# BoatSensor.net
KiCad netlist of a schematic drawn in Altium Designer
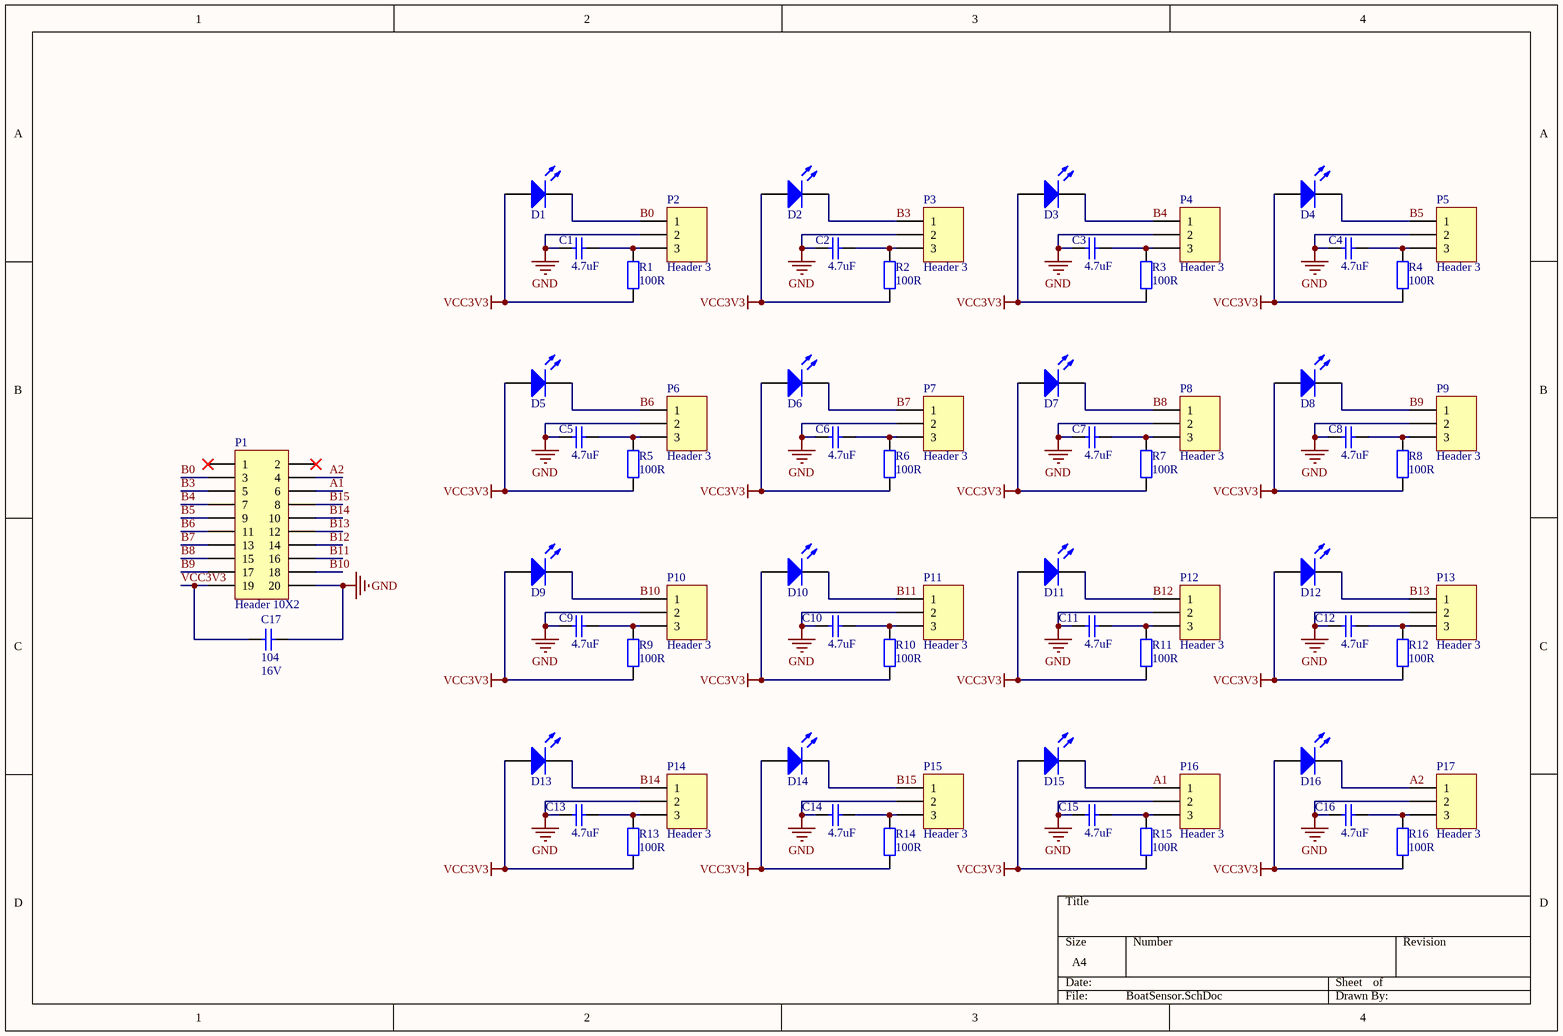
[diagram p0: BoatSensor.SchDoc]

(export (version "E")
  (design (tool "Eeschema 10.0.6"))
  (components
    (comp (ref "C1")
      (value "4.7uF")
      (footprint "0805")
      (fields (field (name "Comment") "Cap_2"))
      (libsource (lib "钦的集成库1") (part "Cap_2"))
    )
    (comp (ref "C2")
      (value "4.7uF")
      (footprint "0805")
      (fields (field (name "Comment") "Cap_2"))
      (libsource (lib "钦的集成库1") (part "Cap_2"))
    )
    (comp (ref "C3")
      (value "4.7uF")
      (footprint "0805")
      (fields (field (name "Comment") "Cap_2"))
      (libsource (lib "钦的集成库1") (part "Cap_2"))
    )
    (comp (ref "C4")
      (value "4.7uF")
      (footprint "0805")
      (fields (field (name "Comment") "Cap_2"))
      (libsource (lib "钦的集成库1") (part "Cap_2"))
    )
    (comp (ref "C5")
      (value "4.7uF")
      (footprint "0805")
      (fields (field (name "Comment") "Cap_2"))
      (libsource (lib "钦的集成库1") (part "Cap_2"))
    )
    (comp (ref "C6")
      (value "4.7uF")
      (footprint "0805")
      (fields (field (name "Comment") "Cap_2"))
      (libsource (lib "钦的集成库1") (part "Cap_2"))
    )
    (comp (ref "C7")
      (value "4.7uF")
      (footprint "0805")
      (fields (field (name "Comment") "Cap_2"))
      (libsource (lib "钦的集成库1") (part "Cap_2"))
    )
    (comp (ref "C8")
      (value "4.7uF")
      (footprint "0805")
      (fields (field (name "Comment") "Cap_2"))
      (libsource (lib "钦的集成库1") (part "Cap_2"))
    )
    (comp (ref "C9")
      (value "4.7uF")
      (footprint "0805")
      (fields (field (name "Comment") "Cap_2"))
      (libsource (lib "钦的集成库1") (part "Cap_2"))
    )
    (comp (ref "C10")
      (value "4.7uF")
      (footprint "0805")
      (fields (field (name "Comment") "Cap_2"))
      (libsource (lib "钦的集成库1") (part "Cap_2"))
    )
    (comp (ref "C11")
      (value "4.7uF")
      (footprint "0805")
      (fields (field (name "Comment") "Cap_2"))
      (libsource (lib "钦的集成库1") (part "Cap_2"))
    )
    (comp (ref "C12")
      (value "4.7uF")
      (footprint "0805")
      (fields (field (name "Comment") "Cap_2"))
      (libsource (lib "钦的集成库1") (part "Cap_2"))
    )
    (comp (ref "C13")
      (value "4.7uF")
      (footprint "0805")
      (fields (field (name "Comment") "Cap_2"))
      (libsource (lib "钦的集成库1") (part "Cap_2"))
    )
    (comp (ref "C14")
      (value "4.7uF")
      (footprint "0805")
      (fields (field (name "Comment") "Cap_2"))
      (libsource (lib "钦的集成库1") (part "Cap_2"))
    )
    (comp (ref "C15")
      (value "4.7uF")
      (footprint "0805")
      (fields (field (name "Comment") "Cap_2"))
      (libsource (lib "钦的集成库1") (part "Cap_2"))
    )
    (comp (ref "C16")
      (value "4.7uF")
      (footprint "0805")
      (fields (field (name "Comment") "Cap_2"))
      (libsource (lib "钦的集成库1") (part "Cap_2"))
    )
    (comp (ref "C17")
      (value "104")
      (footprint "0805")
      (fields
        (field (name "PRESSURE VOLTAGE") "16V")
        (field (name "Comment") "Cap")
        (field (name "原理图绘制者") "刘永钦")
        (field (name "原理图提供者") "刘永钦")
        (field (name "原理图审核人1") "徐鹏飞")
        (field (name "封装0805绘制者") "刘永钦")
        (field (name "封装0805提供者") "刘永钦")
        (field (name "封装0805审核人1") "徐鹏飞")
        (field (name "原理图审核人2") "朱觉文")
        (field (name "封装0805审核人2") "朱觉文")
        (field (name "封装0603绘制者") "刘永钦")
        (field (name "封装0603提供者") "刘永钦")
        (field (name "封装0603审核人1") "朱觉文")
        (field (name "封装0603审核人2") "徐鹏飞")
      )
      (libsource (lib "自动化研究所集成库20170403") (part "Cap"))
    )
    (comp (ref "D1")
      (value "LED")
      (footprint "LED_0805")
      (fields
        (field (name "原理图绘制者") "刘永钦")
        (field (name "原理图提供者") "刘永钦")
        (field (name "原理图审核人1") "徐鹏飞")
        (field (name "封装1210LED绘制者") "刘永钦")
        (field (name "封装1210LED提供者") "刘永钦")
        (field (name "封装1210LED审核人1") "徐鹏飞")
        (field (name "封装LED_3MM绘制者") "刘永钦")
        (field (name "封装LED_3MM提供者") "刘永钦")
        (field (name "封装LED_0805绘制者") "刘永钦")
        (field (name "封装LED_0805提供者") "刘永钦")
        (field (name "封装LED_0805审核人1") "徐鹏飞")
        (field (name "原理图审核人2") "朱觉文")
        (field (name "封装1210LED审核人2") "朱觉文")
        (field (name "封装LED_0805审核人2") "朱觉文")
        (field (name "封装LED_3MM审核者2") "朱觉文")
        (field (name "封装LED0603绘制者") "刘永钦")
        (field (name "封装LED0603审核人2") "朱觉文")
        (field (name "封装LED0603提供者") "刘永钦")
        (field (name "封装LED0603审核人1") "徐鹏飞")
      )
      (libsource (lib "自动化研究所集成库20170403") (part "LED"))
    )
    (comp (ref "D2")
      (value "LED")
      (footprint "LED_0805")
      (fields
        (field (name "原理图绘制者") "刘永钦")
        (field (name "原理图提供者") "刘永钦")
        (field (name "原理图审核人1") "徐鹏飞")
        (field (name "封装1210LED绘制者") "刘永钦")
        (field (name "封装1210LED提供者") "刘永钦")
        (field (name "封装1210LED审核人1") "徐鹏飞")
        (field (name "封装LED_3MM绘制者") "刘永钦")
        (field (name "封装LED_3MM提供者") "刘永钦")
        (field (name "封装LED_0805绘制者") "刘永钦")
        (field (name "封装LED_0805提供者") "刘永钦")
        (field (name "封装LED_0805审核人1") "徐鹏飞")
        (field (name "原理图审核人2") "朱觉文")
        (field (name "封装1210LED审核人2") "朱觉文")
        (field (name "封装LED_0805审核人2") "朱觉文")
        (field (name "封装LED_3MM审核者2") "朱觉文")
        (field (name "封装LED0603绘制者") "刘永钦")
        (field (name "封装LED0603审核人2") "朱觉文")
        (field (name "封装LED0603提供者") "刘永钦")
        (field (name "封装LED0603审核人1") "徐鹏飞")
      )
      (libsource (lib "自动化研究所集成库20170403") (part "LED"))
    )
    (comp (ref "D3")
      (value "LED")
      (footprint "LED_0805")
      (fields
        (field (name "原理图绘制者") "刘永钦")
        (field (name "原理图提供者") "刘永钦")
        (field (name "原理图审核人1") "徐鹏飞")
        (field (name "封装1210LED绘制者") "刘永钦")
        (field (name "封装1210LED提供者") "刘永钦")
        (field (name "封装1210LED审核人1") "徐鹏飞")
        (field (name "封装LED_3MM绘制者") "刘永钦")
        (field (name "封装LED_3MM提供者") "刘永钦")
        (field (name "封装LED_0805绘制者") "刘永钦")
        (field (name "封装LED_0805提供者") "刘永钦")
        (field (name "封装LED_0805审核人1") "徐鹏飞")
        (field (name "原理图审核人2") "朱觉文")
        (field (name "封装1210LED审核人2") "朱觉文")
        (field (name "封装LED_0805审核人2") "朱觉文")
        (field (name "封装LED_3MM审核者2") "朱觉文")
        (field (name "封装LED0603绘制者") "刘永钦")
        (field (name "封装LED0603审核人2") "朱觉文")
        (field (name "封装LED0603提供者") "刘永钦")
        (field (name "封装LED0603审核人1") "徐鹏飞")
      )
      (libsource (lib "自动化研究所集成库20170403") (part "LED"))
    )
    (comp (ref "D4")
      (value "LED")
      (footprint "LED_0805")
      (fields
        (field (name "原理图绘制者") "刘永钦")
        (field (name "原理图提供者") "刘永钦")
        (field (name "原理图审核人1") "徐鹏飞")
        (field (name "封装1210LED绘制者") "刘永钦")
        (field (name "封装1210LED提供者") "刘永钦")
        (field (name "封装1210LED审核人1") "徐鹏飞")
        (field (name "封装LED_3MM绘制者") "刘永钦")
        (field (name "封装LED_3MM提供者") "刘永钦")
        (field (name "封装LED_0805绘制者") "刘永钦")
        (field (name "封装LED_0805提供者") "刘永钦")
        (field (name "封装LED_0805审核人1") "徐鹏飞")
        (field (name "原理图审核人2") "朱觉文")
        (field (name "封装1210LED审核人2") "朱觉文")
        (field (name "封装LED_0805审核人2") "朱觉文")
        (field (name "封装LED_3MM审核者2") "朱觉文")
        (field (name "封装LED0603绘制者") "刘永钦")
        (field (name "封装LED0603审核人2") "朱觉文")
        (field (name "封装LED0603提供者") "刘永钦")
        (field (name "封装LED0603审核人1") "徐鹏飞")
      )
      (libsource (lib "自动化研究所集成库20170403") (part "LED"))
    )
    (comp (ref "D5")
      (value "LED")
      (footprint "LED_0805")
      (fields
        (field (name "原理图绘制者") "刘永钦")
        (field (name "原理图提供者") "刘永钦")
        (field (name "原理图审核人1") "徐鹏飞")
        (field (name "封装1210LED绘制者") "刘永钦")
        (field (name "封装1210LED提供者") "刘永钦")
        (field (name "封装1210LED审核人1") "徐鹏飞")
        (field (name "封装LED_3MM绘制者") "刘永钦")
        (field (name "封装LED_3MM提供者") "刘永钦")
        (field (name "封装LED_0805绘制者") "刘永钦")
        (field (name "封装LED_0805提供者") "刘永钦")
        (field (name "封装LED_0805审核人1") "徐鹏飞")
        (field (name "原理图审核人2") "朱觉文")
        (field (name "封装1210LED审核人2") "朱觉文")
        (field (name "封装LED_0805审核人2") "朱觉文")
        (field (name "封装LED_3MM审核者2") "朱觉文")
        (field (name "封装LED0603绘制者") "刘永钦")
        (field (name "封装LED0603审核人2") "朱觉文")
        (field (name "封装LED0603提供者") "刘永钦")
        (field (name "封装LED0603审核人1") "徐鹏飞")
      )
      (libsource (lib "自动化研究所集成库20170403") (part "LED"))
    )
    (comp (ref "D6")
      (value "LED")
      (footprint "LED_0805")
      (fields
        (field (name "原理图绘制者") "刘永钦")
        (field (name "原理图提供者") "刘永钦")
        (field (name "原理图审核人1") "徐鹏飞")
        (field (name "封装1210LED绘制者") "刘永钦")
        (field (name "封装1210LED提供者") "刘永钦")
        (field (name "封装1210LED审核人1") "徐鹏飞")
        (field (name "封装LED_3MM绘制者") "刘永钦")
        (field (name "封装LED_3MM提供者") "刘永钦")
        (field (name "封装LED_0805绘制者") "刘永钦")
        (field (name "封装LED_0805提供者") "刘永钦")
        (field (name "封装LED_0805审核人1") "徐鹏飞")
        (field (name "原理图审核人2") "朱觉文")
        (field (name "封装1210LED审核人2") "朱觉文")
        (field (name "封装LED_0805审核人2") "朱觉文")
        (field (name "封装LED_3MM审核者2") "朱觉文")
        (field (name "封装LED0603绘制者") "刘永钦")
        (field (name "封装LED0603审核人2") "朱觉文")
        (field (name "封装LED0603提供者") "刘永钦")
        (field (name "封装LED0603审核人1") "徐鹏飞")
      )
      (libsource (lib "自动化研究所集成库20170403") (part "LED"))
    )
    (comp (ref "D7")
      (value "LED")
      (footprint "LED_0805")
      (fields
        (field (name "原理图绘制者") "刘永钦")
        (field (name "原理图提供者") "刘永钦")
        (field (name "原理图审核人1") "徐鹏飞")
        (field (name "封装1210LED绘制者") "刘永钦")
        (field (name "封装1210LED提供者") "刘永钦")
        (field (name "封装1210LED审核人1") "徐鹏飞")
        (field (name "封装LED_3MM绘制者") "刘永钦")
        (field (name "封装LED_3MM提供者") "刘永钦")
        (field (name "封装LED_0805绘制者") "刘永钦")
        (field (name "封装LED_0805提供者") "刘永钦")
        (field (name "封装LED_0805审核人1") "徐鹏飞")
        (field (name "原理图审核人2") "朱觉文")
        (field (name "封装1210LED审核人2") "朱觉文")
        (field (name "封装LED_0805审核人2") "朱觉文")
        (field (name "封装LED_3MM审核者2") "朱觉文")
        (field (name "封装LED0603绘制者") "刘永钦")
        (field (name "封装LED0603审核人2") "朱觉文")
        (field (name "封装LED0603提供者") "刘永钦")
        (field (name "封装LED0603审核人1") "徐鹏飞")
      )
      (libsource (lib "自动化研究所集成库20170403") (part "LED"))
    )
    (comp (ref "D8")
      (value "LED")
      (footprint "LED_0805")
      (fields
        (field (name "原理图绘制者") "刘永钦")
        (field (name "原理图提供者") "刘永钦")
        (field (name "原理图审核人1") "徐鹏飞")
        (field (name "封装1210LED绘制者") "刘永钦")
        (field (name "封装1210LED提供者") "刘永钦")
        (field (name "封装1210LED审核人1") "徐鹏飞")
        (field (name "封装LED_3MM绘制者") "刘永钦")
        (field (name "封装LED_3MM提供者") "刘永钦")
        (field (name "封装LED_0805绘制者") "刘永钦")
        (field (name "封装LED_0805提供者") "刘永钦")
        (field (name "封装LED_0805审核人1") "徐鹏飞")
        (field (name "原理图审核人2") "朱觉文")
        (field (name "封装1210LED审核人2") "朱觉文")
        (field (name "封装LED_0805审核人2") "朱觉文")
        (field (name "封装LED_3MM审核者2") "朱觉文")
        (field (name "封装LED0603绘制者") "刘永钦")
        (field (name "封装LED0603审核人2") "朱觉文")
        (field (name "封装LED0603提供者") "刘永钦")
        (field (name "封装LED0603审核人1") "徐鹏飞")
      )
      (libsource (lib "自动化研究所集成库20170403") (part "LED"))
    )
    (comp (ref "D9")
      (value "LED")
      (footprint "LED_0805")
      (fields
        (field (name "原理图绘制者") "刘永钦")
        (field (name "原理图提供者") "刘永钦")
        (field (name "原理图审核人1") "徐鹏飞")
        (field (name "封装1210LED绘制者") "刘永钦")
        (field (name "封装1210LED提供者") "刘永钦")
        (field (name "封装1210LED审核人1") "徐鹏飞")
        (field (name "封装LED_3MM绘制者") "刘永钦")
        (field (name "封装LED_3MM提供者") "刘永钦")
        (field (name "封装LED_0805绘制者") "刘永钦")
        (field (name "封装LED_0805提供者") "刘永钦")
        (field (name "封装LED_0805审核人1") "徐鹏飞")
        (field (name "原理图审核人2") "朱觉文")
        (field (name "封装1210LED审核人2") "朱觉文")
        (field (name "封装LED_0805审核人2") "朱觉文")
        (field (name "封装LED_3MM审核者2") "朱觉文")
        (field (name "封装LED0603绘制者") "刘永钦")
        (field (name "封装LED0603审核人2") "朱觉文")
        (field (name "封装LED0603提供者") "刘永钦")
        (field (name "封装LED0603审核人1") "徐鹏飞")
      )
      (libsource (lib "自动化研究所集成库20170403") (part "LED"))
    )
    (comp (ref "D10")
      (value "LED")
      (footprint "LED_0805")
      (fields
        (field (name "原理图绘制者") "刘永钦")
        (field (name "原理图提供者") "刘永钦")
        (field (name "原理图审核人1") "徐鹏飞")
        (field (name "封装1210LED绘制者") "刘永钦")
        (field (name "封装1210LED提供者") "刘永钦")
        (field (name "封装1210LED审核人1") "徐鹏飞")
        (field (name "封装LED_3MM绘制者") "刘永钦")
        (field (name "封装LED_3MM提供者") "刘永钦")
        (field (name "封装LED_0805绘制者") "刘永钦")
        (field (name "封装LED_0805提供者") "刘永钦")
        (field (name "封装LED_0805审核人1") "徐鹏飞")
        (field (name "原理图审核人2") "朱觉文")
        (field (name "封装1210LED审核人2") "朱觉文")
        (field (name "封装LED_0805审核人2") "朱觉文")
        (field (name "封装LED_3MM审核者2") "朱觉文")
        (field (name "封装LED0603绘制者") "刘永钦")
        (field (name "封装LED0603审核人2") "朱觉文")
        (field (name "封装LED0603提供者") "刘永钦")
        (field (name "封装LED0603审核人1") "徐鹏飞")
      )
      (libsource (lib "自动化研究所集成库20170403") (part "LED"))
    )
    (comp (ref "D11")
      (value "LED")
      (footprint "LED_0805")
      (fields
        (field (name "原理图绘制者") "刘永钦")
        (field (name "原理图提供者") "刘永钦")
        (field (name "原理图审核人1") "徐鹏飞")
        (field (name "封装1210LED绘制者") "刘永钦")
        (field (name "封装1210LED提供者") "刘永钦")
        (field (name "封装1210LED审核人1") "徐鹏飞")
        (field (name "封装LED_3MM绘制者") "刘永钦")
        (field (name "封装LED_3MM提供者") "刘永钦")
        (field (name "封装LED_0805绘制者") "刘永钦")
        (field (name "封装LED_0805提供者") "刘永钦")
        (field (name "封装LED_0805审核人1") "徐鹏飞")
        (field (name "原理图审核人2") "朱觉文")
        (field (name "封装1210LED审核人2") "朱觉文")
        (field (name "封装LED_0805审核人2") "朱觉文")
        (field (name "封装LED_3MM审核者2") "朱觉文")
        (field (name "封装LED0603绘制者") "刘永钦")
        (field (name "封装LED0603审核人2") "朱觉文")
        (field (name "封装LED0603提供者") "刘永钦")
        (field (name "封装LED0603审核人1") "徐鹏飞")
      )
      (libsource (lib "自动化研究所集成库20170403") (part "LED"))
    )
    (comp (ref "D12")
      (value "LED")
      (footprint "LED_0805")
      (fields
        (field (name "原理图绘制者") "刘永钦")
        (field (name "原理图提供者") "刘永钦")
        (field (name "原理图审核人1") "徐鹏飞")
        (field (name "封装1210LED绘制者") "刘永钦")
        (field (name "封装1210LED提供者") "刘永钦")
        (field (name "封装1210LED审核人1") "徐鹏飞")
        (field (name "封装LED_3MM绘制者") "刘永钦")
        (field (name "封装LED_3MM提供者") "刘永钦")
        (field (name "封装LED_0805绘制者") "刘永钦")
        (field (name "封装LED_0805提供者") "刘永钦")
        (field (name "封装LED_0805审核人1") "徐鹏飞")
        (field (name "原理图审核人2") "朱觉文")
        (field (name "封装1210LED审核人2") "朱觉文")
        (field (name "封装LED_0805审核人2") "朱觉文")
        (field (name "封装LED_3MM审核者2") "朱觉文")
        (field (name "封装LED0603绘制者") "刘永钦")
        (field (name "封装LED0603审核人2") "朱觉文")
        (field (name "封装LED0603提供者") "刘永钦")
        (field (name "封装LED0603审核人1") "徐鹏飞")
      )
      (libsource (lib "自动化研究所集成库20170403") (part "LED"))
    )
    (comp (ref "D13")
      (value "LED")
      (footprint "LED_0805")
      (fields
        (field (name "原理图绘制者") "刘永钦")
        (field (name "原理图提供者") "刘永钦")
        (field (name "原理图审核人1") "徐鹏飞")
        (field (name "封装1210LED绘制者") "刘永钦")
        (field (name "封装1210LED提供者") "刘永钦")
        (field (name "封装1210LED审核人1") "徐鹏飞")
        (field (name "封装LED_3MM绘制者") "刘永钦")
        (field (name "封装LED_3MM提供者") "刘永钦")
        (field (name "封装LED_0805绘制者") "刘永钦")
        (field (name "封装LED_0805提供者") "刘永钦")
        (field (name "封装LED_0805审核人1") "徐鹏飞")
        (field (name "原理图审核人2") "朱觉文")
        (field (name "封装1210LED审核人2") "朱觉文")
        (field (name "封装LED_0805审核人2") "朱觉文")
        (field (name "封装LED_3MM审核者2") "朱觉文")
        (field (name "封装LED0603绘制者") "刘永钦")
        (field (name "封装LED0603审核人2") "朱觉文")
        (field (name "封装LED0603提供者") "刘永钦")
        (field (name "封装LED0603审核人1") "徐鹏飞")
      )
      (libsource (lib "自动化研究所集成库20170403") (part "LED"))
    )
    (comp (ref "D14")
      (value "LED")
      (footprint "LED_0805")
      (fields
        (field (name "原理图绘制者") "刘永钦")
        (field (name "原理图提供者") "刘永钦")
        (field (name "原理图审核人1") "徐鹏飞")
        (field (name "封装1210LED绘制者") "刘永钦")
        (field (name "封装1210LED提供者") "刘永钦")
        (field (name "封装1210LED审核人1") "徐鹏飞")
        (field (name "封装LED_3MM绘制者") "刘永钦")
        (field (name "封装LED_3MM提供者") "刘永钦")
        (field (name "封装LED_0805绘制者") "刘永钦")
        (field (name "封装LED_0805提供者") "刘永钦")
        (field (name "封装LED_0805审核人1") "徐鹏飞")
        (field (name "原理图审核人2") "朱觉文")
        (field (name "封装1210LED审核人2") "朱觉文")
        (field (name "封装LED_0805审核人2") "朱觉文")
        (field (name "封装LED_3MM审核者2") "朱觉文")
        (field (name "封装LED0603绘制者") "刘永钦")
        (field (name "封装LED0603审核人2") "朱觉文")
        (field (name "封装LED0603提供者") "刘永钦")
        (field (name "封装LED0603审核人1") "徐鹏飞")
      )
      (libsource (lib "自动化研究所集成库20170403") (part "LED"))
    )
    (comp (ref "D15")
      (value "LED")
      (footprint "LED_0805")
      (fields
        (field (name "原理图绘制者") "刘永钦")
        (field (name "原理图提供者") "刘永钦")
        (field (name "原理图审核人1") "徐鹏飞")
        (field (name "封装1210LED绘制者") "刘永钦")
        (field (name "封装1210LED提供者") "刘永钦")
        (field (name "封装1210LED审核人1") "徐鹏飞")
        (field (name "封装LED_3MM绘制者") "刘永钦")
        (field (name "封装LED_3MM提供者") "刘永钦")
        (field (name "封装LED_0805绘制者") "刘永钦")
        (field (name "封装LED_0805提供者") "刘永钦")
        (field (name "封装LED_0805审核人1") "徐鹏飞")
        (field (name "原理图审核人2") "朱觉文")
        (field (name "封装1210LED审核人2") "朱觉文")
        (field (name "封装LED_0805审核人2") "朱觉文")
        (field (name "封装LED_3MM审核者2") "朱觉文")
        (field (name "封装LED0603绘制者") "刘永钦")
        (field (name "封装LED0603审核人2") "朱觉文")
        (field (name "封装LED0603提供者") "刘永钦")
        (field (name "封装LED0603审核人1") "徐鹏飞")
      )
      (libsource (lib "自动化研究所集成库20170403") (part "LED"))
    )
    (comp (ref "D16")
      (value "LED")
      (footprint "LED_0805")
      (fields
        (field (name "原理图绘制者") "刘永钦")
        (field (name "原理图提供者") "刘永钦")
        (field (name "原理图审核人1") "徐鹏飞")
        (field (name "封装1210LED绘制者") "刘永钦")
        (field (name "封装1210LED提供者") "刘永钦")
        (field (name "封装1210LED审核人1") "徐鹏飞")
        (field (name "封装LED_3MM绘制者") "刘永钦")
        (field (name "封装LED_3MM提供者") "刘永钦")
        (field (name "封装LED_0805绘制者") "刘永钦")
        (field (name "封装LED_0805提供者") "刘永钦")
        (field (name "封装LED_0805审核人1") "徐鹏飞")
        (field (name "原理图审核人2") "朱觉文")
        (field (name "封装1210LED审核人2") "朱觉文")
        (field (name "封装LED_0805审核人2") "朱觉文")
        (field (name "封装LED_3MM审核者2") "朱觉文")
        (field (name "封装LED0603绘制者") "刘永钦")
        (field (name "封装LED0603审核人2") "朱觉文")
        (field (name "封装LED0603提供者") "刘永钦")
        (field (name "封装LED0603审核人1") "徐鹏飞")
      )
      (libsource (lib "自动化研究所集成库20170403") (part "LED"))
    )
    (comp (ref "P1")
      (value "Header 10X2")
      (footprint "HDR2X10")
      (description "Header, 10-Pin, Dual row")
      (fields (field (name "PUBLISHER") "Altium Limited"))
      (libsource (lib "Miscellaneous Connectors") (part "Header 10X2"))
    )
    (comp (ref "P2")
      (value "Header 3")
      (footprint "HDR1X3")
      (description "Header, 3-Pin")
      (fields (field (name "PUBLISHER") "Altium Limited"))
      (libsource (lib "Miscellaneous Connectors") (part "Header 3"))
    )
    (comp (ref "P3")
      (value "Header 3")
      (footprint "HDR1X3")
      (description "Header, 3-Pin")
      (fields (field (name "PUBLISHER") "Altium Limited"))
      (libsource (lib "Miscellaneous Connectors") (part "Header 3"))
    )
    (comp (ref "P4")
      (value "Header 3")
      (footprint "HDR1X3")
      (description "Header, 3-Pin")
      (fields (field (name "PUBLISHER") "Altium Limited"))
      (libsource (lib "Miscellaneous Connectors") (part "Header 3"))
    )
    (comp (ref "P5")
      (value "Header 3")
      (footprint "HDR1X3")
      (description "Header, 3-Pin")
      (fields (field (name "PUBLISHER") "Altium Limited"))
      (libsource (lib "Miscellaneous Connectors") (part "Header 3"))
    )
    (comp (ref "P6")
      (value "Header 3")
      (footprint "HDR1X3")
      (description "Header, 3-Pin")
      (fields (field (name "PUBLISHER") "Altium Limited"))
      (libsource (lib "Miscellaneous Connectors") (part "Header 3"))
    )
    (comp (ref "P7")
      (value "Header 3")
      (footprint "HDR1X3")
      (description "Header, 3-Pin")
      (fields (field (name "PUBLISHER") "Altium Limited"))
      (libsource (lib "Miscellaneous Connectors") (part "Header 3"))
    )
    (comp (ref "P8")
      (value "Header 3")
      (footprint "HDR1X3")
      (description "Header, 3-Pin")
      (fields (field (name "PUBLISHER") "Altium Limited"))
      (libsource (lib "Miscellaneous Connectors") (part "Header 3"))
    )
    (comp (ref "P9")
      (value "Header 3")
      (footprint "HDR1X3")
      (description "Header, 3-Pin")
      (fields (field (name "PUBLISHER") "Altium Limited"))
      (libsource (lib "Miscellaneous Connectors") (part "Header 3"))
    )
    (comp (ref "P10")
      (value "Header 3")
      (footprint "HDR1X3")
      (description "Header, 3-Pin")
      (fields (field (name "PUBLISHER") "Altium Limited"))
      (libsource (lib "Miscellaneous Connectors") (part "Header 3"))
    )
    (comp (ref "P11")
      (value "Header 3")
      (footprint "HDR1X3")
      (description "Header, 3-Pin")
      (fields (field (name "PUBLISHER") "Altium Limited"))
      (libsource (lib "Miscellaneous Connectors") (part "Header 3"))
    )
    (comp (ref "P12")
      (value "Header 3")
      (footprint "HDR1X3")
      (description "Header, 3-Pin")
      (fields (field (name "PUBLISHER") "Altium Limited"))
      (libsource (lib "Miscellaneous Connectors") (part "Header 3"))
    )
    (comp (ref "P13")
      (value "Header 3")
      (footprint "HDR1X3")
      (description "Header, 3-Pin")
      (fields (field (name "PUBLISHER") "Altium Limited"))
      (libsource (lib "Miscellaneous Connectors") (part "Header 3"))
    )
    (comp (ref "P14")
      (value "Header 3")
      (footprint "HDR1X3")
      (description "Header, 3-Pin")
      (fields (field (name "PUBLISHER") "Altium Limited"))
      (libsource (lib "Miscellaneous Connectors") (part "Header 3"))
    )
    (comp (ref "P15")
      (value "Header 3")
      (footprint "HDR1X3")
      (description "Header, 3-Pin")
      (fields (field (name "PUBLISHER") "Altium Limited"))
      (libsource (lib "Miscellaneous Connectors") (part "Header 3"))
    )
    (comp (ref "P16")
      (value "Header 3")
      (footprint "HDR1X3")
      (description "Header, 3-Pin")
      (fields (field (name "PUBLISHER") "Altium Limited"))
      (libsource (lib "Miscellaneous Connectors") (part "Header 3"))
    )
    (comp (ref "P17")
      (value "Header 3")
      (footprint "HDR1X3")
      (description "Header, 3-Pin")
      (fields (field (name "PUBLISHER") "Altium Limited"))
      (libsource (lib "Miscellaneous Connectors") (part "Header 3"))
    )
    (comp (ref "R1")
      (value "100R")
      (footprint "0805")
      (fields (field (name "Comment") "Res_"))
      (libsource (lib "钦的集成库1") (part "Res_"))
    )
    (comp (ref "R2")
      (value "100R")
      (footprint "0805")
      (fields (field (name "Comment") "Res_"))
      (libsource (lib "钦的集成库1") (part "Res_"))
    )
    (comp (ref "R3")
      (value "100R")
      (footprint "0805")
      (fields (field (name "Comment") "Res_"))
      (libsource (lib "钦的集成库1") (part "Res_"))
    )
    (comp (ref "R4")
      (value "100R")
      (footprint "0805")
      (fields (field (name "Comment") "Res_"))
      (libsource (lib "钦的集成库1") (part "Res_"))
    )
    (comp (ref "R5")
      (value "100R")
      (footprint "0805")
      (fields (field (name "Comment") "Res_"))
      (libsource (lib "钦的集成库1") (part "Res_"))
    )
    (comp (ref "R6")
      (value "100R")
      (footprint "0805")
      (fields (field (name "Comment") "Res_"))
      (libsource (lib "钦的集成库1") (part "Res_"))
    )
    (comp (ref "R7")
      (value "100R")
      (footprint "0805")
      (fields (field (name "Comment") "Res_"))
      (libsource (lib "钦的集成库1") (part "Res_"))
    )
    (comp (ref "R8")
      (value "100R")
      (footprint "0805")
      (fields (field (name "Comment") "Res_"))
      (libsource (lib "钦的集成库1") (part "Res_"))
    )
    (comp (ref "R9")
      (value "100R")
      (footprint "0805")
      (fields (field (name "Comment") "Res_"))
      (libsource (lib "钦的集成库1") (part "Res_"))
    )
    (comp (ref "R10")
      (value "100R")
      (footprint "0805")
      (fields (field (name "Comment") "Res_"))
      (libsource (lib "钦的集成库1") (part "Res_"))
    )
    (comp (ref "R11")
      (value "100R")
      (footprint "0805")
      (fields (field (name "Comment") "Res_"))
      (libsource (lib "钦的集成库1") (part "Res_"))
    )
    (comp (ref "R12")
      (value "100R")
      (footprint "0805")
      (fields (field (name "Comment") "Res_"))
      (libsource (lib "钦的集成库1") (part "Res_"))
    )
    (comp (ref "R13")
      (value "100R")
      (footprint "0805")
      (fields (field (name "Comment") "Res_"))
      (libsource (lib "钦的集成库1") (part "Res_"))
    )
    (comp (ref "R14")
      (value "100R")
      (footprint "0805")
      (fields (field (name "Comment") "Res_"))
      (libsource (lib "钦的集成库1") (part "Res_"))
    )
    (comp (ref "R15")
      (value "100R")
      (footprint "0805")
      (fields (field (name "Comment") "Res_"))
      (libsource (lib "钦的集成库1") (part "Res_"))
    )
    (comp (ref "R16")
      (value "100R")
      (footprint "0805")
      (fields (field (name "Comment") "Res_"))
      (libsource (lib "钦的集成库1") (part "Res_"))
    )
  )
  (nets
    (net (code "1") (name "/A1") (class "Default")
      (node (ref "D15") (pin "2") (pinfunction "K_2") (pintype "passive"))
      (node (ref "P1") (pin "6") (pinfunction "6_6") (pintype "passive"))
      (node (ref "P16") (pin "1") (pinfunction "1_1") (pintype "passive"))
    )
    (net (code "2") (name "/A2") (class "Default")
      (node (ref "D16") (pin "2") (pinfunction "K_2") (pintype "passive"))
      (node (ref "P1") (pin "4") (pinfunction "4_4") (pintype "passive"))
      (node (ref "P17") (pin "1") (pinfunction "1_1") (pintype "passive"))
    )
    (net (code "3") (name "/B0") (class "Default")
      (node (ref "D1") (pin "2") (pinfunction "K_2") (pintype "passive"))
      (node (ref "P1") (pin "3") (pinfunction "3_3") (pintype "passive"))
      (node (ref "P2") (pin "1") (pinfunction "1_1") (pintype "passive"))
    )
    (net (code "4") (name "/B3") (class "Default")
      (node (ref "D2") (pin "2") (pinfunction "K_2") (pintype "passive"))
      (node (ref "P1") (pin "5") (pinfunction "5_5") (pintype "passive"))
      (node (ref "P3") (pin "1") (pinfunction "1_1") (pintype "passive"))
    )
    (net (code "5") (name "/B4") (class "Default")
      (node (ref "D3") (pin "2") (pinfunction "K_2") (pintype "passive"))
      (node (ref "P1") (pin "7") (pinfunction "7_7") (pintype "passive"))
      (node (ref "P4") (pin "1") (pinfunction "1_1") (pintype "passive"))
    )
    (net (code "6") (name "/B5") (class "Default")
      (node (ref "D4") (pin "2") (pinfunction "K_2") (pintype "passive"))
      (node (ref "P1") (pin "9") (pinfunction "9_9") (pintype "passive"))
      (node (ref "P5") (pin "1") (pinfunction "1_1") (pintype "passive"))
    )
    (net (code "7") (name "/B6") (class "Default")
      (node (ref "D5") (pin "2") (pinfunction "K_2") (pintype "passive"))
      (node (ref "P1") (pin "11") (pinfunction "11_11") (pintype "passive"))
      (node (ref "P6") (pin "1") (pinfunction "1_1") (pintype "passive"))
    )
    (net (code "8") (name "/B7") (class "Default")
      (node (ref "D6") (pin "2") (pinfunction "K_2") (pintype "passive"))
      (node (ref "P1") (pin "13") (pinfunction "13_13") (pintype "passive"))
      (node (ref "P7") (pin "1") (pinfunction "1_1") (pintype "passive"))
    )
    (net (code "9") (name "/B8") (class "Default")
      (node (ref "D7") (pin "2") (pinfunction "K_2") (pintype "passive"))
      (node (ref "P1") (pin "15") (pinfunction "15_15") (pintype "passive"))
      (node (ref "P8") (pin "1") (pinfunction "1_1") (pintype "passive"))
    )
    (net (code "10") (name "/B9") (class "Default")
      (node (ref "D8") (pin "2") (pinfunction "K_2") (pintype "passive"))
      (node (ref "P1") (pin "17") (pinfunction "17_17") (pintype "passive"))
      (node (ref "P9") (pin "1") (pinfunction "1_1") (pintype "passive"))
    )
    (net (code "11") (name "/B10") (class "Default")
      (node (ref "D9") (pin "2") (pinfunction "K_2") (pintype "passive"))
      (node (ref "P1") (pin "18") (pinfunction "18_18") (pintype "passive"))
      (node (ref "P10") (pin "1") (pinfunction "1_1") (pintype "passive"))
    )
    (net (code "12") (name "/B11") (class "Default")
      (node (ref "D10") (pin "2") (pinfunction "K_2") (pintype "passive"))
      (node (ref "P1") (pin "16") (pinfunction "16_16") (pintype "passive"))
      (node (ref "P11") (pin "1") (pinfunction "1_1") (pintype "passive"))
    )
    (net (code "13") (name "/B12") (class "Default")
      (node (ref "D11") (pin "2") (pinfunction "K_2") (pintype "passive"))
      (node (ref "P1") (pin "14") (pinfunction "14_14") (pintype "passive"))
      (node (ref "P12") (pin "1") (pinfunction "1_1") (pintype "passive"))
    )
    (net (code "14") (name "/B13") (class "Default")
      (node (ref "D12") (pin "2") (pinfunction "K_2") (pintype "passive"))
      (node (ref "P1") (pin "12") (pinfunction "12_12") (pintype "passive"))
      (node (ref "P13") (pin "1") (pinfunction "1_1") (pintype "passive"))
    )
    (net (code "15") (name "/B14") (class "Default")
      (node (ref "D13") (pin "2") (pinfunction "K_2") (pintype "passive"))
      (node (ref "P1") (pin "10") (pinfunction "10_10") (pintype "passive"))
      (node (ref "P14") (pin "1") (pinfunction "1_1") (pintype "passive"))
    )
    (net (code "16") (name "/B15") (class "Default")
      (node (ref "D14") (pin "2") (pinfunction "K_2") (pintype "passive"))
      (node (ref "P1") (pin "8") (pinfunction "8_8") (pintype "passive"))
      (node (ref "P15") (pin "1") (pinfunction "1_1") (pintype "passive"))
    )
    (net (code "17") (name "GND") (class "Default")
      (node (ref "C1") (pin "2") (pinfunction "2_2") (pintype "passive"))
      (node (ref "C10") (pin "2") (pinfunction "2_2") (pintype "passive"))
      (node (ref "C11") (pin "2") (pinfunction "2_2") (pintype "passive"))
      (node (ref "C12") (pin "2") (pinfunction "2_2") (pintype "passive"))
      (node (ref "C13") (pin "2") (pinfunction "2_2") (pintype "passive"))
      (node (ref "C14") (pin "2") (pinfunction "2_2") (pintype "passive"))
      (node (ref "C15") (pin "2") (pinfunction "2_2") (pintype "passive"))
      (node (ref "C16") (pin "2") (pinfunction "2_2") (pintype "passive"))
      (node (ref "C17") (pin "2") (pinfunction "2_2") (pintype "passive"))
      (node (ref "C2") (pin "2") (pinfunction "2_2") (pintype "passive"))
      (node (ref "C3") (pin "2") (pinfunction "2_2") (pintype "passive"))
      (node (ref "C4") (pin "2") (pinfunction "2_2") (pintype "passive"))
      (node (ref "C5") (pin "2") (pinfunction "2_2") (pintype "passive"))
      (node (ref "C6") (pin "2") (pinfunction "2_2") (pintype "passive"))
      (node (ref "C7") (pin "2") (pinfunction "2_2") (pintype "passive"))
      (node (ref "C8") (pin "2") (pinfunction "2_2") (pintype "passive"))
      (node (ref "C9") (pin "2") (pinfunction "2_2") (pintype "passive"))
      (node (ref "P1") (pin "20") (pinfunction "20_20") (pintype "passive"))
      (node (ref "P10") (pin "2") (pinfunction "2_2") (pintype "passive"))
      (node (ref "P11") (pin "2") (pinfunction "2_2") (pintype "passive"))
      (node (ref "P12") (pin "2") (pinfunction "2_2") (pintype "passive"))
      (node (ref "P13") (pin "2") (pinfunction "2_2") (pintype "passive"))
      (node (ref "P14") (pin "2") (pinfunction "2_2") (pintype "passive"))
      (node (ref "P15") (pin "2") (pinfunction "2_2") (pintype "passive"))
      (node (ref "P16") (pin "2") (pinfunction "2_2") (pintype "passive"))
      (node (ref "P17") (pin "2") (pinfunction "2_2") (pintype "passive"))
      (node (ref "P2") (pin "2") (pinfunction "2_2") (pintype "passive"))
      (node (ref "P3") (pin "2") (pinfunction "2_2") (pintype "passive"))
      (node (ref "P4") (pin "2") (pinfunction "2_2") (pintype "passive"))
      (node (ref "P5") (pin "2") (pinfunction "2_2") (pintype "passive"))
      (node (ref "P6") (pin "2") (pinfunction "2_2") (pintype "passive"))
      (node (ref "P7") (pin "2") (pinfunction "2_2") (pintype "passive"))
      (node (ref "P8") (pin "2") (pinfunction "2_2") (pintype "passive"))
      (node (ref "P9") (pin "2") (pinfunction "2_2") (pintype "passive"))
    )
    (net (code "18") (name "Net-(C1-Pad1)") (class "Default")
      (node (ref "C1") (pin "1") (pinfunction "1_1") (pintype "passive"))
      (node (ref "P2") (pin "3") (pinfunction "3_3") (pintype "passive"))
      (node (ref "R1") (pin "1") (pinfunction "1_1") (pintype "passive"))
    )
    (net (code "19") (name "Net-(C2-Pad1)") (class "Default")
      (node (ref "C2") (pin "1") (pinfunction "1_1") (pintype "passive"))
      (node (ref "P3") (pin "3") (pinfunction "3_3") (pintype "passive"))
      (node (ref "R2") (pin "1") (pinfunction "1_1") (pintype "passive"))
    )
    (net (code "20") (name "Net-(C3-Pad1)") (class "Default")
      (node (ref "C3") (pin "1") (pinfunction "1_1") (pintype "passive"))
      (node (ref "P4") (pin "3") (pinfunction "3_3") (pintype "passive"))
      (node (ref "R3") (pin "1") (pinfunction "1_1") (pintype "passive"))
    )
    (net (code "21") (name "Net-(C4-Pad1)") (class "Default")
      (node (ref "C4") (pin "1") (pinfunction "1_1") (pintype "passive"))
      (node (ref "P5") (pin "3") (pinfunction "3_3") (pintype "passive"))
      (node (ref "R4") (pin "1") (pinfunction "1_1") (pintype "passive"))
    )
    (net (code "22") (name "Net-(C5-Pad1)") (class "Default")
      (node (ref "C5") (pin "1") (pinfunction "1_1") (pintype "passive"))
      (node (ref "P6") (pin "3") (pinfunction "3_3") (pintype "passive"))
      (node (ref "R5") (pin "1") (pinfunction "1_1") (pintype "passive"))
    )
    (net (code "23") (name "Net-(C6-Pad1)") (class "Default")
      (node (ref "C6") (pin "1") (pinfunction "1_1") (pintype "passive"))
      (node (ref "P7") (pin "3") (pinfunction "3_3") (pintype "passive"))
      (node (ref "R6") (pin "1") (pinfunction "1_1") (pintype "passive"))
    )
    (net (code "24") (name "Net-(C7-Pad1)") (class "Default")
      (node (ref "C7") (pin "1") (pinfunction "1_1") (pintype "passive"))
      (node (ref "P8") (pin "3") (pinfunction "3_3") (pintype "passive"))
      (node (ref "R7") (pin "1") (pinfunction "1_1") (pintype "passive"))
    )
    (net (code "25") (name "Net-(C8-Pad1)") (class "Default")
      (node (ref "C8") (pin "1") (pinfunction "1_1") (pintype "passive"))
      (node (ref "P9") (pin "3") (pinfunction "3_3") (pintype "passive"))
      (node (ref "R8") (pin "1") (pinfunction "1_1") (pintype "passive"))
    )
    (net (code "26") (name "Net-(C9-Pad1)") (class "Default")
      (node (ref "C9") (pin "1") (pinfunction "1_1") (pintype "passive"))
      (node (ref "P10") (pin "3") (pinfunction "3_3") (pintype "passive"))
      (node (ref "R9") (pin "1") (pinfunction "1_1") (pintype "passive"))
    )
    (net (code "27") (name "Net-(C10-Pad1)") (class "Default")
      (node (ref "C10") (pin "1") (pinfunction "1_1") (pintype "passive"))
      (node (ref "P11") (pin "3") (pinfunction "3_3") (pintype "passive"))
      (node (ref "R10") (pin "1") (pinfunction "1_1") (pintype "passive"))
    )
    (net (code "28") (name "Net-(C11-Pad1)") (class "Default")
      (node (ref "C11") (pin "1") (pinfunction "1_1") (pintype "passive"))
      (node (ref "P12") (pin "3") (pinfunction "3_3") (pintype "passive"))
      (node (ref "R11") (pin "1") (pinfunction "1_1") (pintype "passive"))
    )
    (net (code "29") (name "Net-(C12-Pad1)") (class "Default")
      (node (ref "C12") (pin "1") (pinfunction "1_1") (pintype "passive"))
      (node (ref "P13") (pin "3") (pinfunction "3_3") (pintype "passive"))
      (node (ref "R12") (pin "1") (pinfunction "1_1") (pintype "passive"))
    )
    (net (code "30") (name "Net-(C13-Pad1)") (class "Default")
      (node (ref "C13") (pin "1") (pinfunction "1_1") (pintype "passive"))
      (node (ref "P14") (pin "3") (pinfunction "3_3") (pintype "passive"))
      (node (ref "R13") (pin "1") (pinfunction "1_1") (pintype "passive"))
    )
    (net (code "31") (name "Net-(C14-Pad1)") (class "Default")
      (node (ref "C14") (pin "1") (pinfunction "1_1") (pintype "passive"))
      (node (ref "P15") (pin "3") (pinfunction "3_3") (pintype "passive"))
      (node (ref "R14") (pin "1") (pinfunction "1_1") (pintype "passive"))
    )
    (net (code "32") (name "Net-(C15-Pad1)") (class "Default")
      (node (ref "C15") (pin "1") (pinfunction "1_1") (pintype "passive"))
      (node (ref "P16") (pin "3") (pinfunction "3_3") (pintype "passive"))
      (node (ref "R15") (pin "1") (pinfunction "1_1") (pintype "passive"))
    )
    (net (code "33") (name "Net-(C16-Pad1)") (class "Default")
      (node (ref "C16") (pin "1") (pinfunction "1_1") (pintype "passive"))
      (node (ref "P17") (pin "3") (pinfunction "3_3") (pintype "passive"))
      (node (ref "R16") (pin "1") (pinfunction "1_1") (pintype "passive"))
    )
    (net (code "34") (name "VCC3V3") (class "Default")
      (node (ref "C17") (pin "1") (pinfunction "1_1") (pintype "passive"))
      (node (ref "D1") (pin "1") (pinfunction "A_1") (pintype "passive"))
      (node (ref "D10") (pin "1") (pinfunction "A_1") (pintype "passive"))
      (node (ref "D11") (pin "1") (pinfunction "A_1") (pintype "passive"))
      (node (ref "D12") (pin "1") (pinfunction "A_1") (pintype "passive"))
      (node (ref "D13") (pin "1") (pinfunction "A_1") (pintype "passive"))
      (node (ref "D14") (pin "1") (pinfunction "A_1") (pintype "passive"))
      (node (ref "D15") (pin "1") (pinfunction "A_1") (pintype "passive"))
      (node (ref "D16") (pin "1") (pinfunction "A_1") (pintype "passive"))
      (node (ref "D2") (pin "1") (pinfunction "A_1") (pintype "passive"))
      (node (ref "D3") (pin "1") (pinfunction "A_1") (pintype "passive"))
      (node (ref "D4") (pin "1") (pinfunction "A_1") (pintype "passive"))
      (node (ref "D5") (pin "1") (pinfunction "A_1") (pintype "passive"))
      (node (ref "D6") (pin "1") (pinfunction "A_1") (pintype "passive"))
      (node (ref "D7") (pin "1") (pinfunction "A_1") (pintype "passive"))
      (node (ref "D8") (pin "1") (pinfunction "A_1") (pintype "passive"))
      (node (ref "D9") (pin "1") (pinfunction "A_1") (pintype "passive"))
      (node (ref "P1") (pin "19") (pinfunction "19_19") (pintype "passive"))
      (node (ref "R1") (pin "2") (pinfunction "2_2") (pintype "passive"))
      (node (ref "R10") (pin "2") (pinfunction "2_2") (pintype "passive"))
      (node (ref "R11") (pin "2") (pinfunction "2_2") (pintype "passive"))
      (node (ref "R12") (pin "2") (pinfunction "2_2") (pintype "passive"))
      (node (ref "R13") (pin "2") (pinfunction "2_2") (pintype "passive"))
      (node (ref "R14") (pin "2") (pinfunction "2_2") (pintype "passive"))
      (node (ref "R15") (pin "2") (pinfunction "2_2") (pintype "passive"))
      (node (ref "R16") (pin "2") (pinfunction "2_2") (pintype "passive"))
      (node (ref "R2") (pin "2") (pinfunction "2_2") (pintype "passive"))
      (node (ref "R3") (pin "2") (pinfunction "2_2") (pintype "passive"))
      (node (ref "R4") (pin "2") (pinfunction "2_2") (pintype "passive"))
      (node (ref "R5") (pin "2") (pinfunction "2_2") (pintype "passive"))
      (node (ref "R6") (pin "2") (pinfunction "2_2") (pintype "passive"))
      (node (ref "R7") (pin "2") (pinfunction "2_2") (pintype "passive"))
      (node (ref "R8") (pin "2") (pinfunction "2_2") (pintype "passive"))
      (node (ref "R9") (pin "2") (pinfunction "2_2") (pintype "passive"))
    )
    (net (code "35") (name "unconnected-(P1-Pad1)") (class "Default")
      (node (ref "P1") (pin "1") (pinfunction "1_1") (pintype "passive+no_connect"))
    )
    (net (code "36") (name "unconnected-(P1-Pad2)") (class "Default")
      (node (ref "P1") (pin "2") (pinfunction "2_2") (pintype "passive+no_connect"))
    )
  )
)
